# main_SMD_FET.net
KiCad netlist of a schematic drawn in EAGLE
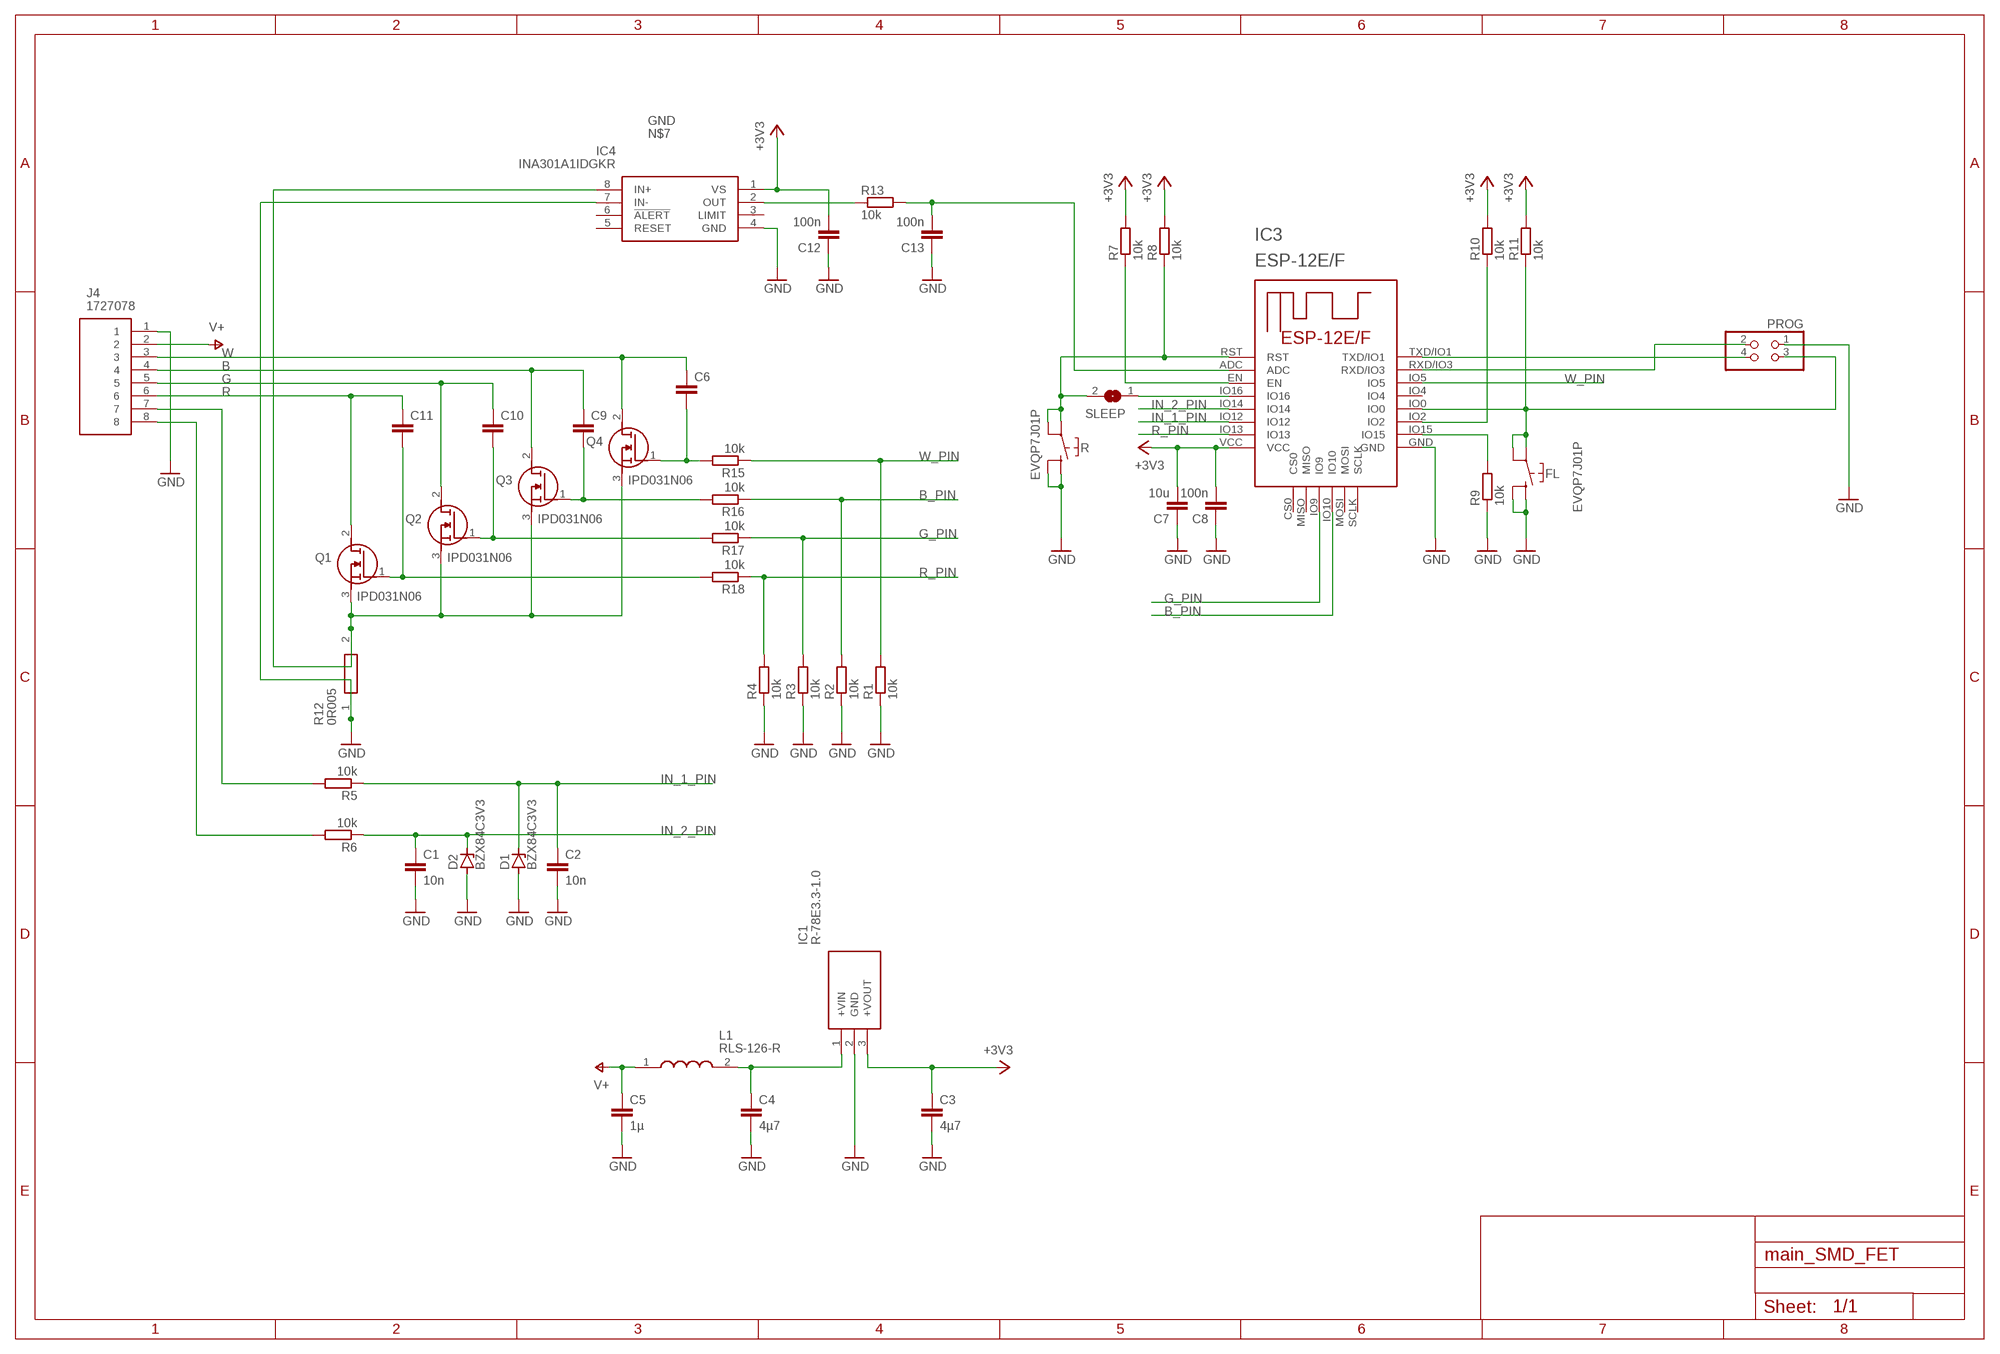
[diagram p0: schematic, sheet 1]

(export (version "E")
  (design (tool "Eeschema 10.0.6"))
  (components
    (comp (ref "C1")
      (value "10n")
      (footprint "eagle-import:C0603")
      (libsource (lib "eagle-import") (part "C-EUC0603"))
    )
    (comp (ref "C2")
      (value "10n")
      (footprint "eagle-import:C0603")
      (libsource (lib "eagle-import") (part "C-EUC0603"))
    )
    (comp (ref "C3")
      (value "4µ7")
      (footprint "eagle-import:C0603")
      (libsource (lib "eagle-import") (part "C-EUC0603"))
    )
    (comp (ref "C4")
      (value "4µ7")
      (footprint "eagle-import:C1206")
      (libsource (lib "eagle-import") (part "C-EUC1206"))
    )
    (comp (ref "C5")
      (value "1µ")
      (footprint "eagle-import:C1206")
      (libsource (lib "eagle-import") (part "C-EUC1206"))
    )
    (comp (ref "C6")
      (value "C-EUC0402")
      (footprint "eagle-import:C0402")
      (libsource (lib "eagle-import") (part "C-EUC0402"))
    )
    (comp (ref "C7")
      (value "10u")
      (footprint "eagle-import:C0603")
      (libsource (lib "eagle-import") (part "C-EUC0603"))
    )
    (comp (ref "C8")
      (value "100n")
      (footprint "eagle-import:C0603")
      (libsource (lib "eagle-import") (part "C-EUC0603"))
    )
    (comp (ref "C9")
      (value "C-EUC0402")
      (footprint "eagle-import:C0402")
      (libsource (lib "eagle-import") (part "C-EUC0402"))
    )
    (comp (ref "C10")
      (value "C-EUC0402")
      (footprint "eagle-import:C0402")
      (libsource (lib "eagle-import") (part "C-EUC0402"))
    )
    (comp (ref "C11")
      (value "C-EUC0402")
      (footprint "eagle-import:C0402")
      (libsource (lib "eagle-import") (part "C-EUC0402"))
    )
    (comp (ref "C12")
      (value "100n")
      (footprint "eagle-import:C0603")
      (libsource (lib "eagle-import") (part "C-EUC0603"))
    )
    (comp (ref "C13")
      (value "100n")
      (footprint "eagle-import:C0603")
      (libsource (lib "eagle-import") (part "C-EUC0603"))
    )
    (comp (ref "D1")
      (value "BZX84C3V3")
      (footprint "eagle-import:TO236")
      (libsource (lib "eagle-import") (part "BZX84CSMD"))
    )
    (comp (ref "D2")
      (value "BZX84C3V3")
      (footprint "eagle-import:TO236")
      (libsource (lib "eagle-import") (part "BZX84CSMD"))
    )
    (comp (ref "FL")
      (value "EVQP7J01P")
      (footprint "eagle-import:EVQP7J01P")
      (libsource (lib "eagle-import") (part "EVQP7J01P"))
    )
    (comp (ref "IC1")
      (value "R-78E3.3-1.0")
      (footprint "eagle-import:R78E3310")
      (fields (field (name "MOUSER_PART_NUMBER") "919-R-78E3.3-1.0"))
      (libsource (lib "eagle-import") (part "R-78E3.3-1.0"))
    )
    (comp (ref "IC3")
      (value "ESP-12E/F")
      (footprint "eagle-import:ESP-12E")
      (libsource (lib "eagle-import") (part "ESP-12E/F"))
    )
    (comp (ref "IC4")
      (value "INA301A1IDGKR")
      (footprint "eagle-import:SOP65P490X110-8N")
      (fields (field (name "MOUSER_PART_NUMBER") "595-INA301A1IDGKR"))
      (libsource (lib "eagle-import") (part "INA301A1IDGKR"))
    )
    (comp (ref "J4")
      (value "1727078")
      (footprint "eagle-import:SHDR8W90P0X381_1X8_3047X730X86")
      (fields (field (name "MOUSER_PART_NUMBER") "651-1727078") (field (name "RS_PART_NUMBER") "2204399"))
      (libsource (lib "eagle-import") (part "1727078"))
    )
    (comp (ref "L1")
      (value "RLS-126-R")
      (footprint "eagle-import:RLS126R")
      (fields (field (name "MOUSER_PART_NUMBER") "919-RLS-126-R"))
      (libsource (lib "eagle-import") (part "RLS-126-R"))
    )
    (comp (ref "PROG")
      (value "PINHD-2X2")
      (footprint "eagle-import:2X02")
      (libsource (lib "eagle-import") (part "PINHD-2X2"))
    )
    (comp (ref "Q1")
      (value "IPD031N06")
      (footprint "eagle-import:IPD031N06L3GATMA1")
      (fields
        (field (name "ARROW_PART_NUMBER") "IPD031N06L3GATMA1")
        (field (name "MOUSER_PART_NUMBER") "726-IPD031N06L3GATMA")
      )
      (libsource (lib "eagle-import") (part "IPD031N06L3GATMA1"))
    )
    (comp (ref "Q2")
      (value "IPD031N06")
      (footprint "eagle-import:IPD031N06L3GATMA1")
      (fields
        (field (name "ARROW_PART_NUMBER") "IPD031N06L3GATMA1")
        (field (name "MOUSER_PART_NUMBER") "726-IPD031N06L3GATMA")
      )
      (libsource (lib "eagle-import") (part "IPD031N06L3GATMA1"))
    )
    (comp (ref "Q3")
      (value "IPD031N06")
      (footprint "eagle-import:IPD031N06L3GATMA1")
      (fields
        (field (name "ARROW_PART_NUMBER") "IPD031N06L3GATMA1")
        (field (name "MOUSER_PART_NUMBER") "726-IPD031N06L3GATMA")
      )
      (libsource (lib "eagle-import") (part "IPD031N06L3GATMA1"))
    )
    (comp (ref "Q4")
      (value "IPD031N06")
      (footprint "eagle-import:IPD031N06L3GATMA1")
      (fields
        (field (name "ARROW_PART_NUMBER") "IPD031N06L3GATMA1")
        (field (name "MOUSER_PART_NUMBER") "726-IPD031N06L3GATMA")
      )
      (libsource (lib "eagle-import") (part "IPD031N06L3GATMA1"))
    )
    (comp (ref "R")
      (value "EVQP7J01P")
      (footprint "eagle-import:EVQP7J01P")
      (libsource (lib "eagle-import") (part "EVQP7J01P"))
    )
    (comp (ref "R1")
      (value "10k")
      (footprint "eagle-import:R0402")
      (libsource (lib "eagle-import") (part "R-EU_R0402"))
    )
    (comp (ref "R2")
      (value "10k")
      (footprint "eagle-import:R0402")
      (libsource (lib "eagle-import") (part "R-EU_R0402"))
    )
    (comp (ref "R3")
      (value "10k")
      (footprint "eagle-import:R0402")
      (libsource (lib "eagle-import") (part "R-EU_R0402"))
    )
    (comp (ref "R4")
      (value "10k")
      (footprint "eagle-import:R0402")
      (libsource (lib "eagle-import") (part "R-EU_R0402"))
    )
    (comp (ref "R5")
      (value "10k")
      (footprint "eagle-import:R0603")
      (libsource (lib "eagle-import") (part "R-EU_R0603"))
    )
    (comp (ref "R6")
      (value "10k")
      (footprint "eagle-import:R0603")
      (libsource (lib "eagle-import") (part "R-EU_R0603"))
    )
    (comp (ref "R7")
      (value "10k")
      (footprint "eagle-import:R0402")
      (libsource (lib "eagle-import") (part "R-EU_R0402"))
    )
    (comp (ref "R8")
      (value "10k")
      (footprint "eagle-import:R0402")
      (libsource (lib "eagle-import") (part "R-EU_R0402"))
    )
    (comp (ref "R9")
      (value "10k")
      (footprint "eagle-import:R0402")
      (libsource (lib "eagle-import") (part "R-EU_R0402"))
    )
    (comp (ref "R10")
      (value "10k")
      (footprint "eagle-import:R0402")
      (libsource (lib "eagle-import") (part "R-EU_R0402"))
    )
    (comp (ref "R11")
      (value "10k")
      (footprint "eagle-import:R0402")
      (libsource (lib "eagle-import") (part "R-EU_R0402"))
    )
    (comp (ref "R12")
      (value "0R005")
      (footprint "eagle-import:RESC3216X68N")
      (fields
        (field (name "MANUFACTURER_PART_NUMBER") "PCS1206DR0100ET")
        (field (name "MOUSER_PART_NUMBER") "588-PCS1206DR0100ET")
      )
      (libsource (lib "eagle-import") (part "PCS1206DR0100ET"))
    )
    (comp (ref "R13")
      (value "10k")
      (footprint "eagle-import:R0402")
      (libsource (lib "eagle-import") (part "R-EU_R0402"))
    )
    (comp (ref "R15")
      (value "10k")
      (footprint "eagle-import:R0402")
      (libsource (lib "eagle-import") (part "R-EU_R0402"))
    )
    (comp (ref "R16")
      (value "10k")
      (footprint "eagle-import:R0402")
      (libsource (lib "eagle-import") (part "R-EU_R0402"))
    )
    (comp (ref "R17")
      (value "10k")
      (footprint "eagle-import:R0402")
      (libsource (lib "eagle-import") (part "R-EU_R0402"))
    )
    (comp (ref "R18")
      (value "10k")
      (footprint "eagle-import:R0402")
      (libsource (lib "eagle-import") (part "R-EU_R0402"))
    )
    (comp (ref "SLEEP")
      (value "SJ")
      (footprint "eagle-import:SJ")
      (libsource (lib "eagle-import") (part "SJ"))
    )
  )
  (nets
    (net (code "1") (name "+3V3") (class "Default")
      (node (ref "C12") (pin "2") (pinfunction "2_2") (pintype "passive"))
      (node (ref "C3") (pin "1") (pinfunction "1_1") (pintype "passive"))
      (node (ref "C7") (pin "2") (pinfunction "2_2") (pintype "passive"))
      (node (ref "C8") (pin "2") (pinfunction "2_2") (pintype "passive"))
      (node (ref "IC1") (pin "3") (pinfunction "+VOUT_3") (pintype "bidirectional"))
      (node (ref "IC3") (pin "VCC") (pinfunction "VCC_VCC") (pintype "power_in"))
      (node (ref "IC4") (pin "1") (pinfunction "VS_1") (pintype "bidirectional"))
      (node (ref "R10") (pin "2") (pinfunction "2_2") (pintype "passive"))
      (node (ref "R11") (pin "2") (pinfunction "2_2") (pintype "passive"))
      (node (ref "R7") (pin "2") (pinfunction "2_2") (pintype "passive"))
      (node (ref "R8") (pin "2") (pinfunction "2_2") (pintype "passive"))
    )
    (net (code "2") (name "/B") (class "Default")
      (node (ref "C9") (pin "1") (pinfunction "1_1") (pintype "passive"))
      (node (ref "J4") (pin "4") (pinfunction "4_4") (pintype "bidirectional"))
      (node (ref "Q3") (pin "2") (pinfunction "D_2") (pintype "bidirectional"))
    )
    (net (code "3") (name "/B_PIN") (class "Default")
      (node (ref "IC3") (pin "IO10") (pinfunction "IO10_IO10") (pintype "bidirectional"))
      (node (ref "R16") (pin "1") (pinfunction "1_1") (pintype "passive"))
      (node (ref "R2") (pin "2") (pinfunction "2_2") (pintype "passive"))
    )
    (net (code "4") (name "/G") (class "Default")
      (node (ref "C10") (pin "1") (pinfunction "1_1") (pintype "passive"))
      (node (ref "J4") (pin "5") (pinfunction "5_5") (pintype "bidirectional"))
      (node (ref "Q2") (pin "2") (pinfunction "D_2") (pintype "bidirectional"))
    )
    (net (code "5") (name "/G_PIN") (class "Default")
      (node (ref "IC3") (pin "IO9") (pinfunction "IO9_IO9") (pintype "bidirectional"))
      (node (ref "R17") (pin "1") (pinfunction "1_1") (pintype "passive"))
      (node (ref "R3") (pin "2") (pinfunction "2_2") (pintype "passive"))
    )
    (net (code "6") (name "/IN_1_PIN") (class "Default")
      (node (ref "C2") (pin "1") (pinfunction "1_1") (pintype "passive"))
      (node (ref "D1") (pin "C") (pinfunction "C_C") (pintype "passive"))
      (node (ref "IC3") (pin "IO12") (pinfunction "IO12_IO12") (pintype "bidirectional"))
      (node (ref "R5") (pin "1") (pinfunction "1_1") (pintype "passive"))
    )
    (net (code "7") (name "/IN_2_PIN") (class "Default")
      (node (ref "C1") (pin "1") (pinfunction "1_1") (pintype "passive"))
      (node (ref "D2") (pin "C") (pinfunction "C_C") (pintype "passive"))
      (node (ref "IC3") (pin "IO14") (pinfunction "IO14_IO14") (pintype "bidirectional"))
      (node (ref "R6") (pin "1") (pinfunction "1_1") (pintype "passive"))
    )
    (net (code "8") (name "/N$7") (class "Default")
      (node (ref "IC4") (pin "8") (pinfunction "IN+_8") (pintype "bidirectional"))
      (node (ref "Q1") (pin "3") (pinfunction "S_3") (pintype "bidirectional"))
      (node (ref "Q2") (pin "3") (pinfunction "S_3") (pintype "bidirectional"))
      (node (ref "Q3") (pin "3") (pinfunction "S_3") (pintype "bidirectional"))
      (node (ref "Q4") (pin "3") (pinfunction "S_3") (pintype "bidirectional"))
      (node (ref "R12") (pin "2") (pinfunction "2_2") (pintype "bidirectional"))
    )
    (net (code "9") (name "/R") (class "Default")
      (node (ref "C11") (pin "1") (pinfunction "1_1") (pintype "passive"))
      (node (ref "J4") (pin "6") (pinfunction "6_6") (pintype "bidirectional"))
      (node (ref "Q1") (pin "2") (pinfunction "D_2") (pintype "bidirectional"))
    )
    (net (code "10") (name "/R_PIN") (class "Default")
      (node (ref "IC3") (pin "IO13") (pinfunction "IO13_IO13") (pintype "bidirectional"))
      (node (ref "R18") (pin "1") (pinfunction "1_1") (pintype "passive"))
      (node (ref "R4") (pin "2") (pinfunction "2_2") (pintype "passive"))
    )
    (net (code "11") (name "/W") (class "Default")
      (node (ref "C6") (pin "1") (pinfunction "1_1") (pintype "passive"))
      (node (ref "J4") (pin "3") (pinfunction "3_3") (pintype "bidirectional"))
      (node (ref "Q4") (pin "2") (pinfunction "D_2") (pintype "bidirectional"))
    )
    (net (code "12") (name "/W_PIN") (class "Default")
      (node (ref "IC3") (pin "IO5") (pinfunction "IO5_IO5") (pintype "bidirectional"))
      (node (ref "R1") (pin "2") (pinfunction "2_2") (pintype "passive"))
      (node (ref "R15") (pin "1") (pinfunction "1_1") (pintype "passive"))
    )
    (net (code "13") (name "GND") (class "Default")
      (node (ref "C1") (pin "2") (pinfunction "2_2") (pintype "passive"))
      (node (ref "C12") (pin "1") (pinfunction "1_1") (pintype "passive"))
      (node (ref "C13") (pin "1") (pinfunction "1_1") (pintype "passive"))
      (node (ref "C2") (pin "2") (pinfunction "2_2") (pintype "passive"))
      (node (ref "C3") (pin "2") (pinfunction "2_2") (pintype "passive"))
      (node (ref "C4") (pin "2") (pinfunction "2_2") (pintype "passive"))
      (node (ref "C5") (pin "2") (pinfunction "2_2") (pintype "passive"))
      (node (ref "C7") (pin "1") (pinfunction "1_1") (pintype "passive"))
      (node (ref "C8") (pin "1") (pinfunction "1_1") (pintype "passive"))
      (node (ref "D1") (pin "A") (pinfunction "A_A") (pintype "passive"))
      (node (ref "D2") (pin "A") (pinfunction "A_A") (pintype "passive"))
      (node (ref "FL") (pin "A2") (pinfunction "COM_1_A2") (pintype "bidirectional"))
      (node (ref "FL") (pin "B2") (pinfunction "COM_2_B2") (pintype "bidirectional"))
      (node (ref "IC1") (pin "2") (pinfunction "GND_2") (pintype "bidirectional"))
      (node (ref "IC3") (pin "GND") (pinfunction "GND_GND") (pintype "power_in"))
      (node (ref "IC4") (pin "4") (pinfunction "GND_4") (pintype "bidirectional"))
      (node (ref "IC4") (pin "7") (pinfunction "IN-_7") (pintype "bidirectional"))
      (node (ref "J4") (pin "1") (pinfunction "1_1") (pintype "bidirectional"))
      (node (ref "PROG") (pin "1") (pinfunction "1_1") (pintype "passive"))
      (node (ref "R") (pin "A2") (pinfunction "COM_1_A2") (pintype "bidirectional"))
      (node (ref "R") (pin "B2") (pinfunction "COM_2_B2") (pintype "bidirectional"))
      (node (ref "R1") (pin "1") (pinfunction "1_1") (pintype "passive"))
      (node (ref "R12") (pin "1") (pinfunction "1_1") (pintype "bidirectional"))
      (node (ref "R2") (pin "1") (pinfunction "1_1") (pintype "passive"))
      (node (ref "R3") (pin "1") (pinfunction "1_1") (pintype "passive"))
      (node (ref "R4") (pin "1") (pinfunction "1_1") (pintype "passive"))
      (node (ref "R9") (pin "1") (pinfunction "1_1") (pintype "passive"))
    )
    (net (code "14") (name "Net-(C13-Pad2)") (class "Default")
      (node (ref "C13") (pin "2") (pinfunction "2_2") (pintype "passive"))
      (node (ref "IC3") (pin "ADC") (pinfunction "ADC_ADC") (pintype "bidirectional"))
      (node (ref "R13") (pin "2") (pinfunction "2_2") (pintype "passive"))
    )
    (net (code "15") (name "Net-(FL-NO_1)") (class "Default")
      (node (ref "FL") (pin "A1") (pinfunction "NO_1_A1") (pintype "bidirectional"))
      (node (ref "FL") (pin "B1") (pinfunction "NO_2_B1") (pintype "bidirectional"))
      (node (ref "IC3") (pin "IO0") (pinfunction "IO0_IO0") (pintype "bidirectional"))
      (node (ref "PROG") (pin "3") (pinfunction "3_3") (pintype "passive"))
      (node (ref "R11") (pin "1") (pinfunction "1_1") (pintype "passive"))
    )
    (net (code "16") (name "Net-(IC1-+VIN)") (class "Default")
      (node (ref "C4") (pin "1") (pinfunction "1_1") (pintype "passive"))
      (node (ref "IC1") (pin "1") (pinfunction "+VIN_1") (pintype "bidirectional"))
      (node (ref "L1") (pin "2") (pinfunction "2_2") (pintype "bidirectional"))
    )
    (net (code "17") (name "Net-(IC3-PadEN)") (class "Default")
      (node (ref "IC3") (pin "EN") (pinfunction "EN_EN") (pintype "bidirectional"))
      (node (ref "R7") (pin "1") (pinfunction "1_1") (pintype "passive"))
    )
    (net (code "18") (name "Net-(IC3-PadIO2)") (class "Default")
      (node (ref "IC3") (pin "IO2") (pinfunction "IO2_IO2") (pintype "bidirectional"))
      (node (ref "R10") (pin "1") (pinfunction "1_1") (pintype "passive"))
    )
    (net (code "19") (name "Net-(IC3-PadIO15)") (class "Default")
      (node (ref "IC3") (pin "IO15") (pinfunction "IO15_IO15") (pintype "bidirectional"))
      (node (ref "R9") (pin "2") (pinfunction "2_2") (pintype "passive"))
    )
    (net (code "20") (name "Net-(IC3-PadIO16)") (class "Default")
      (node (ref "IC3") (pin "IO16") (pinfunction "IO16_IO16") (pintype "bidirectional"))
      (node (ref "SLEEP") (pin "1") (pinfunction "1_1") (pintype "passive"))
    )
    (net (code "21") (name "Net-(IC3-PadRXD{slash}IO3)") (class "Default")
      (node (ref "IC3") (pin "RXD/IO3") (pinfunction "RXD/IO3_RXD/IO3") (pintype "bidirectional"))
      (node (ref "PROG") (pin "2") (pinfunction "2_2") (pintype "passive"))
    )
    (net (code "22") (name "Net-(IC3-PadTXD{slash}IO1)") (class "Default")
      (node (ref "IC3") (pin "TXD/IO1") (pinfunction "TXD/IO1_TXD/IO1") (pintype "bidirectional"))
      (node (ref "PROG") (pin "4") (pinfunction "4_4") (pintype "passive"))
    )
    (net (code "23") (name "Net-(IC4-OUT)") (class "Default")
      (node (ref "IC4") (pin "2") (pinfunction "OUT_2") (pintype "bidirectional"))
      (node (ref "R13") (pin "1") (pinfunction "1_1") (pintype "passive"))
    )
    (net (code "24") (name "Net-(J4-Pad7)") (class "Default")
      (node (ref "J4") (pin "7") (pinfunction "7_7") (pintype "bidirectional"))
      (node (ref "R5") (pin "2") (pinfunction "2_2") (pintype "passive"))
    )
    (net (code "25") (name "Net-(J4-Pad8)") (class "Default")
      (node (ref "J4") (pin "8") (pinfunction "8_8") (pintype "bidirectional"))
      (node (ref "R6") (pin "2") (pinfunction "2_2") (pintype "passive"))
    )
    (net (code "26") (name "Net-(Q1-G)") (class "Default")
      (node (ref "C11") (pin "2") (pinfunction "2_2") (pintype "passive"))
      (node (ref "Q1") (pin "1") (pinfunction "G_1") (pintype "bidirectional"))
      (node (ref "R18") (pin "2") (pinfunction "2_2") (pintype "passive"))
    )
    (net (code "27") (name "Net-(Q2-G)") (class "Default")
      (node (ref "C10") (pin "2") (pinfunction "2_2") (pintype "passive"))
      (node (ref "Q2") (pin "1") (pinfunction "G_1") (pintype "bidirectional"))
      (node (ref "R17") (pin "2") (pinfunction "2_2") (pintype "passive"))
    )
    (net (code "28") (name "Net-(Q3-G)") (class "Default")
      (node (ref "C9") (pin "2") (pinfunction "2_2") (pintype "passive"))
      (node (ref "Q3") (pin "1") (pinfunction "G_1") (pintype "bidirectional"))
      (node (ref "R16") (pin "2") (pinfunction "2_2") (pintype "passive"))
    )
    (net (code "29") (name "Net-(Q4-G)") (class "Default")
      (node (ref "C6") (pin "2") (pinfunction "2_2") (pintype "passive"))
      (node (ref "Q4") (pin "1") (pinfunction "G_1") (pintype "bidirectional"))
      (node (ref "R15") (pin "2") (pinfunction "2_2") (pintype "passive"))
    )
    (net (code "30") (name "Net-(R-NO_1)") (class "Default")
      (node (ref "IC3") (pin "RST") (pinfunction "RST_RST") (pintype "input"))
      (node (ref "R") (pin "A1") (pinfunction "NO_1_A1") (pintype "bidirectional"))
      (node (ref "R") (pin "B1") (pinfunction "NO_2_B1") (pintype "bidirectional"))
      (node (ref "R8") (pin "1") (pinfunction "1_1") (pintype "passive"))
      (node (ref "SLEEP") (pin "2") (pinfunction "2_2") (pintype "passive"))
    )
    (net (code "31") (name "V+") (class "Default")
      (node (ref "C5") (pin "1") (pinfunction "1_1") (pintype "passive"))
      (node (ref "J4") (pin "2") (pinfunction "2_2") (pintype "bidirectional"))
      (node (ref "L1") (pin "1") (pinfunction "1_1") (pintype "bidirectional"))
    )
    (net (code "32") (name "unconnected-(IC3-PadCS0)") (class "Default")
      (node (ref "IC3") (pin "CS0") (pinfunction "CS0_CS0") (pintype "bidirectional"))
    )
    (net (code "33") (name "unconnected-(IC3-PadIO4)") (class "Default")
      (node (ref "IC3") (pin "IO4") (pinfunction "IO4_IO4") (pintype "bidirectional"))
    )
    (net (code "34") (name "unconnected-(IC3-PadMISO)") (class "Default")
      (node (ref "IC3") (pin "MISO") (pinfunction "MISO_MISO") (pintype "bidirectional"))
    )
    (net (code "35") (name "unconnected-(IC3-PadMOSI)") (class "Default")
      (node (ref "IC3") (pin "MOSI") (pinfunction "MOSI_MOSI") (pintype "bidirectional"))
    )
    (net (code "36") (name "unconnected-(IC3-PadSCLK)") (class "Default")
      (node (ref "IC3") (pin "SCLK") (pinfunction "SCLK_SCLK") (pintype "bidirectional"))
    )
    (net (code "37") (name "unconnected-(IC4-LIMIT-Pad3)") (class "Default")
      (node (ref "IC4") (pin "3") (pinfunction "LIMIT_3") (pintype "bidirectional"))
    )
    (net (code "38") (name "unconnected-(IC4-RESET-Pad5)") (class "Default")
      (node (ref "IC4") (pin "5") (pinfunction "RESET_5") (pintype "bidirectional"))
    )
    (net (code "39") (name "unconnected-(IC4-~{ALERT}-Pad6)") (class "Default")
      (node (ref "IC4") (pin "6") (pinfunction "~{ALERT}_6") (pintype "bidirectional"))
    )
  )
)
